# room_interface.net
KiCad netlist of a schematic drawn in EAGLE
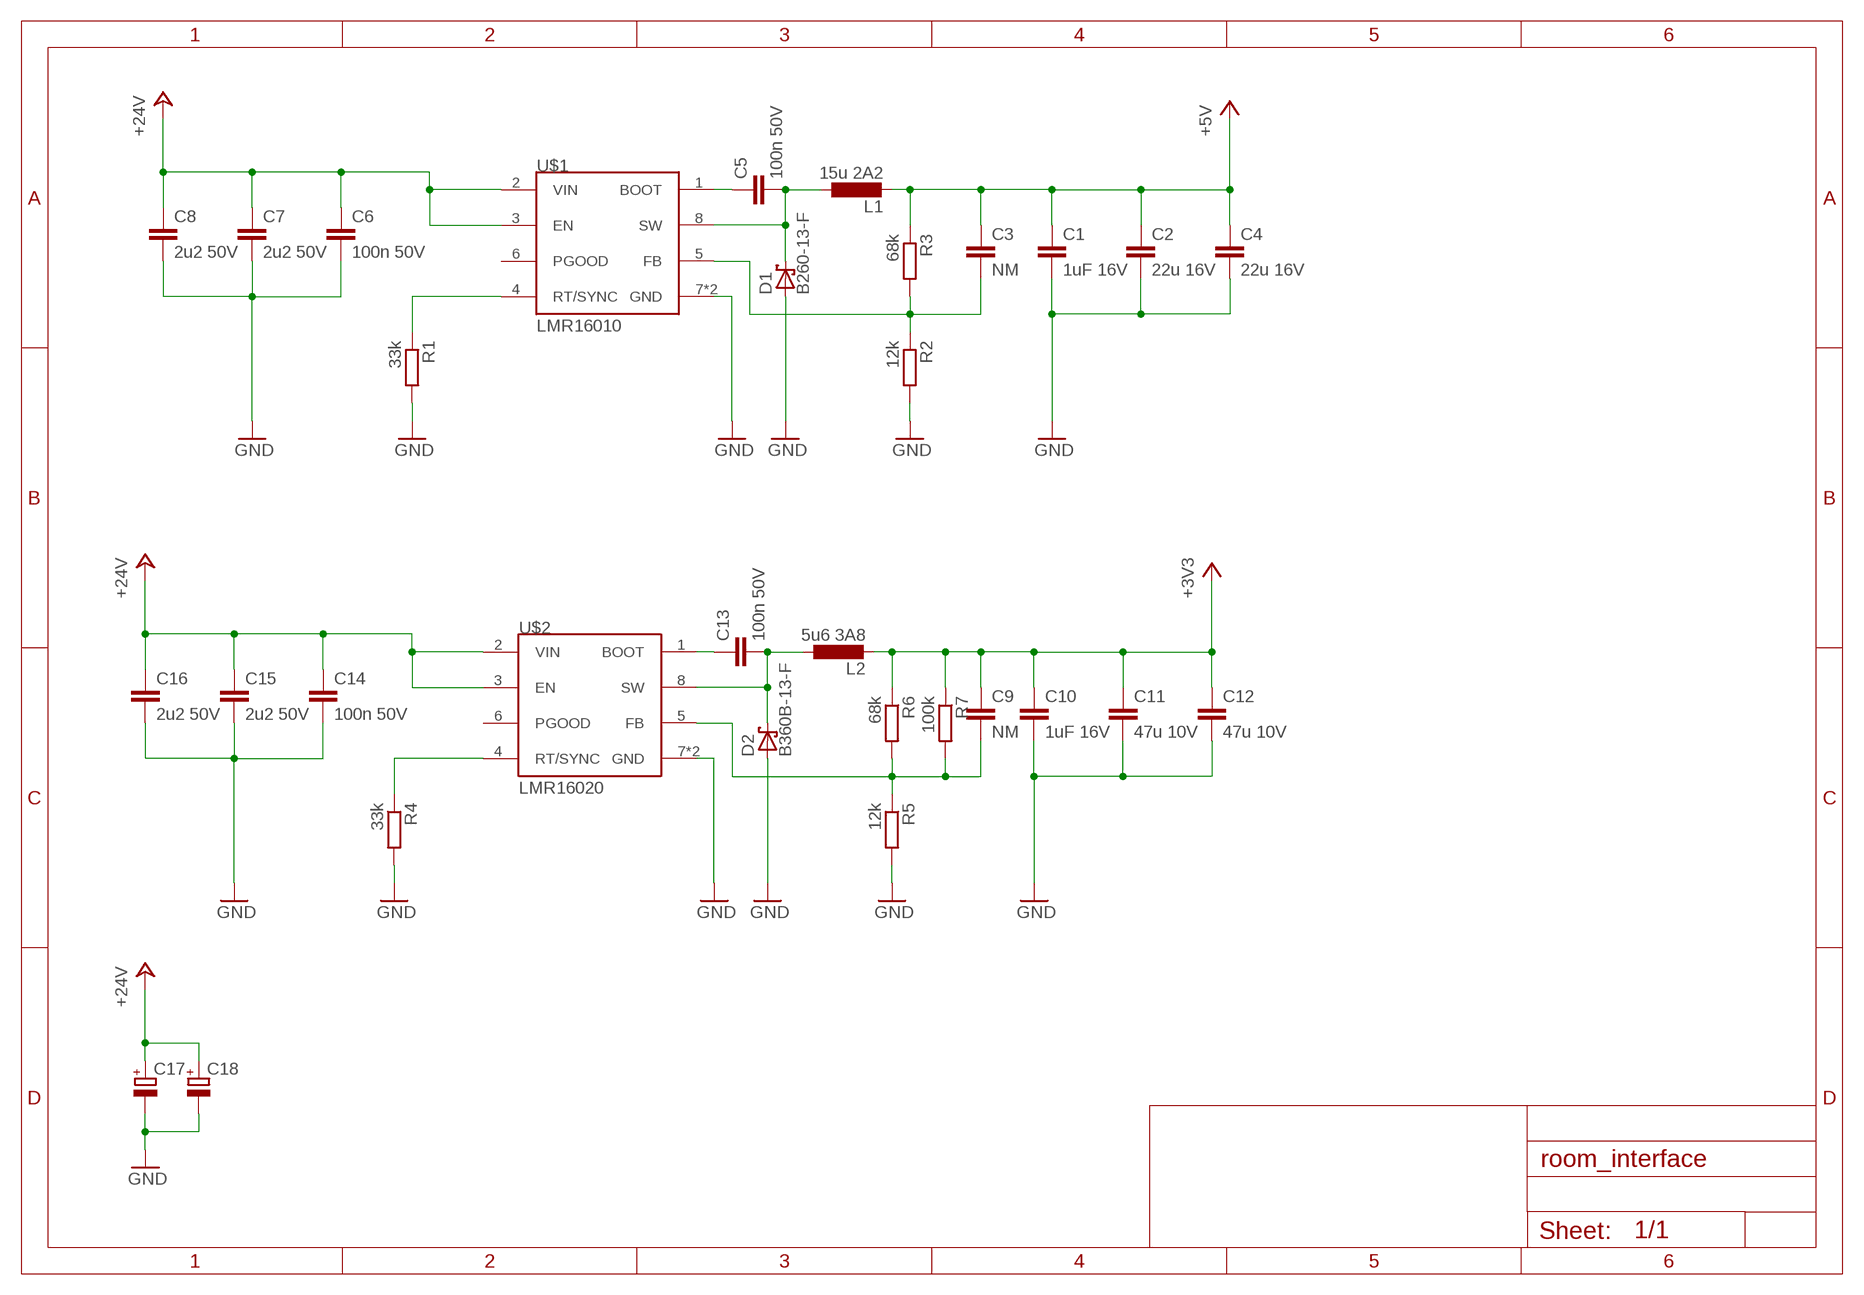
[diagram p0: schematic, sheet 1]

(export (version "E")
  (design (tool "Eeschema 10.0.6"))
  (components
    (comp (ref "C1")
      (value "1uF 16V")
      (footprint "eagle-import:C0805")
      (libsource (lib "eagle-import") (part "C-EUC0805"))
    )
    (comp (ref "C2")
      (value "22u 16V")
      (footprint "eagle-import:C1210")
      (libsource (lib "eagle-import") (part "C-EUC1210"))
    )
    (comp (ref "C3")
      (value "NM")
      (footprint "eagle-import:C1206")
      (libsource (lib "eagle-import") (part "C-EUC1206"))
    )
    (comp (ref "C4")
      (value "22u 16V")
      (footprint "eagle-import:C1210")
      (libsource (lib "eagle-import") (part "C-EUC1210"))
    )
    (comp (ref "C5")
      (value "100n 50V")
      (footprint "eagle-import:C1206")
      (libsource (lib "eagle-import") (part "C-EUC1206"))
    )
    (comp (ref "C6")
      (value "100n 50V")
      (footprint "eagle-import:C1206")
      (libsource (lib "eagle-import") (part "C-EUC1206"))
    )
    (comp (ref "C7")
      (value "2u2 50V")
      (footprint "eagle-import:C1206")
      (libsource (lib "eagle-import") (part "C-EUC1206"))
    )
    (comp (ref "C8")
      (value "2u2 50V")
      (footprint "eagle-import:C1206")
      (libsource (lib "eagle-import") (part "C-EUC1206"))
    )
    (comp (ref "C9")
      (value "NM")
      (footprint "eagle-import:C1206")
      (libsource (lib "eagle-import") (part "C-EUC1206"))
    )
    (comp (ref "C10")
      (value "1uF 16V")
      (footprint "eagle-import:C0805")
      (libsource (lib "eagle-import") (part "C-EUC0805"))
    )
    (comp (ref "C11")
      (value "47u 10V")
      (footprint "eagle-import:C1210")
      (libsource (lib "eagle-import") (part "C-EUC1210"))
    )
    (comp (ref "C12")
      (value "47u 10V")
      (footprint "eagle-import:C1210")
      (libsource (lib "eagle-import") (part "C-EUC1210"))
    )
    (comp (ref "C13")
      (value "100n 50V")
      (footprint "eagle-import:C1206")
      (libsource (lib "eagle-import") (part "C-EUC1206"))
    )
    (comp (ref "C14")
      (value "100n 50V")
      (footprint "eagle-import:C1206")
      (libsource (lib "eagle-import") (part "C-EUC1206"))
    )
    (comp (ref "C15")
      (value "2u2 50V")
      (footprint "eagle-import:C1206")
      (libsource (lib "eagle-import") (part "C-EUC1206"))
    )
    (comp (ref "C16")
      (value "2u2 50V")
      (footprint "eagle-import:C1206")
      (libsource (lib "eagle-import") (part "C-EUC1206"))
    )
    (comp (ref "C17")
      (value "CPOL-EUUD-5X5,8")
      (footprint "eagle-import:UD-5X5,8_NICHICON")
      (libsource (lib "eagle-import") (part "CPOL-EUUD-5X5,8"))
    )
    (comp (ref "C18")
      (value "CPOL-EUUD-5X5,8")
      (footprint "eagle-import:UD-5X5,8_NICHICON")
      (libsource (lib "eagle-import") (part "CPOL-EUUD-5X5,8"))
    )
    (comp (ref "D1")
      (value "B260-13-F")
      (footprint "eagle-import:SMB")
      (libsource (lib "eagle-import") (part "MBRS130LT3"))
    )
    (comp (ref "D2")
      (value "B360B-13-F")
      (footprint "eagle-import:SMB")
      (libsource (lib "eagle-import") (part "MBRS130LT3"))
    )
    (comp (ref "L1")
      (value "15u 2A2")
      (footprint "eagle-import:SLF10145T-150M2R2-PF")
      (libsource (lib "eagle-import") (part "SLF10145T-150M2R2-PF"))
    )
    (comp (ref "L2")
      (value "5u6 3A8")
      (footprint "eagle-import:SLF10145T-150M2R2-PF")
      (libsource (lib "eagle-import") (part "SLF10145T-150M2R2-PF"))
    )
    (comp (ref "R1")
      (value "33k")
      (footprint "eagle-import:R1206")
      (libsource (lib "eagle-import") (part "R-EU_R1206"))
    )
    (comp (ref "R2")
      (value "12k")
      (footprint "eagle-import:R1206")
      (libsource (lib "eagle-import") (part "R-EU_R1206"))
    )
    (comp (ref "R3")
      (value "68k")
      (footprint "eagle-import:R1206")
      (libsource (lib "eagle-import") (part "R-EU_R1206"))
    )
    (comp (ref "R4")
      (value "33k")
      (footprint "eagle-import:R1206")
      (libsource (lib "eagle-import") (part "R-EU_R1206"))
    )
    (comp (ref "R5")
      (value "12k")
      (footprint "eagle-import:R1206")
      (libsource (lib "eagle-import") (part "R-EU_R1206"))
    )
    (comp (ref "R6")
      (value "68k")
      (footprint "eagle-import:R1206")
      (libsource (lib "eagle-import") (part "R-EU_R1206"))
    )
    (comp (ref "R7")
      (value "100k")
      (footprint "eagle-import:R1206")
      (libsource (lib "eagle-import") (part "R-EU_R1206"))
    )
    (comp (ref "U$1")
      (value "LMR16010")
      (footprint "eagle-import:SOIC127P600X170-8N")
      (libsource (lib "eagle-import") (part "LMR16010"))
    )
    (comp (ref "U$2")
      (value "LMR16020")
      (footprint "eagle-import:SOIC127P600X170-8N")
      (libsource (lib "eagle-import") (part "LMR16020"))
    )
  )
  (nets
    (net (code "1") (name "+3V3") (class "Default")
      (node (ref "C10") (pin "1") (pinfunction "1_1") (pintype "passive"))
      (node (ref "C11") (pin "1") (pinfunction "1_1") (pintype "passive"))
      (node (ref "C12") (pin "1") (pinfunction "1_1") (pintype "passive"))
      (node (ref "C9") (pin "1") (pinfunction "1_1") (pintype "passive"))
      (node (ref "L2") (pin "P$2") (pinfunction "2_P$2") (pintype "passive"))
      (node (ref "R6") (pin "1") (pinfunction "1_1") (pintype "passive"))
      (node (ref "R7") (pin "1") (pinfunction "1_1") (pintype "passive"))
    )
    (net (code "2") (name "+5V") (class "Default")
      (node (ref "C1") (pin "1") (pinfunction "1_1") (pintype "passive"))
      (node (ref "C2") (pin "1") (pinfunction "1_1") (pintype "passive"))
      (node (ref "C3") (pin "1") (pinfunction "1_1") (pintype "passive"))
      (node (ref "C4") (pin "1") (pinfunction "1_1") (pintype "passive"))
      (node (ref "L1") (pin "P$2") (pinfunction "2_P$2") (pintype "passive"))
      (node (ref "R3") (pin "1") (pinfunction "1_1") (pintype "passive"))
    )
    (net (code "3") (name "+24V") (class "Default")
      (node (ref "C14") (pin "1") (pinfunction "1_1") (pintype "passive"))
      (node (ref "C15") (pin "1") (pinfunction "1_1") (pintype "passive"))
      (node (ref "C16") (pin "1") (pinfunction "1_1") (pintype "passive"))
      (node (ref "C17") (pin "+") (pinfunction "+_+") (pintype "passive"))
      (node (ref "C18") (pin "+") (pinfunction "+_+") (pintype "passive"))
      (node (ref "C6") (pin "1") (pinfunction "1_1") (pintype "passive"))
      (node (ref "C7") (pin "1") (pinfunction "1_1") (pintype "passive"))
      (node (ref "C8") (pin "1") (pinfunction "1_1") (pintype "passive"))
      (node (ref "U$1") (pin "2") (pinfunction "VIN_2") (pintype "power_in"))
      (node (ref "U$1") (pin "3") (pinfunction "EN_3") (pintype "input"))
      (node (ref "U$2") (pin "2") (pinfunction "VIN_2") (pintype "power_in"))
      (node (ref "U$2") (pin "3") (pinfunction "EN_3") (pintype "input"))
    )
    (net (code "4") (name "GND") (class "Default")
      (node (ref "C1") (pin "2") (pinfunction "2_2") (pintype "passive"))
      (node (ref "C10") (pin "2") (pinfunction "2_2") (pintype "passive"))
      (node (ref "C11") (pin "2") (pinfunction "2_2") (pintype "passive"))
      (node (ref "C12") (pin "2") (pinfunction "2_2") (pintype "passive"))
      (node (ref "C14") (pin "2") (pinfunction "2_2") (pintype "passive"))
      (node (ref "C15") (pin "2") (pinfunction "2_2") (pintype "passive"))
      (node (ref "C16") (pin "2") (pinfunction "2_2") (pintype "passive"))
      (node (ref "C17") (pin "-") (pinfunction "-_-") (pintype "passive"))
      (node (ref "C18") (pin "-") (pinfunction "-_-") (pintype "passive"))
      (node (ref "C2") (pin "2") (pinfunction "2_2") (pintype "passive"))
      (node (ref "C4") (pin "2") (pinfunction "2_2") (pintype "passive"))
      (node (ref "C6") (pin "2") (pinfunction "2_2") (pintype "passive"))
      (node (ref "C7") (pin "2") (pinfunction "2_2") (pintype "passive"))
      (node (ref "C8") (pin "2") (pinfunction "2_2") (pintype "passive"))
      (node (ref "D1") (pin "A") (pinfunction "A_A") (pintype "passive"))
      (node (ref "D2") (pin "A") (pinfunction "A_A") (pintype "passive"))
      (node (ref "R1") (pin "2") (pinfunction "2_2") (pintype "passive"))
      (node (ref "R2") (pin "2") (pinfunction "2_2") (pintype "passive"))
      (node (ref "R4") (pin "2") (pinfunction "2_2") (pintype "passive"))
      (node (ref "R5") (pin "2") (pinfunction "2_2") (pintype "passive"))
      (node (ref "U$1") (pin "7") (pinfunction "GND_7") (pintype "power_in"))
      (node (ref "U$1") (pin "9") (pinfunction "GND_9") (pintype "power_in"))
      (node (ref "U$2") (pin "7") (pinfunction "GND_7") (pintype "power_in"))
      (node (ref "U$2") (pin "9") (pinfunction "GND_9") (pintype "power_in"))
    )
    (net (code "5") (name "Net-(L1-1)") (class "Default")
      (node (ref "C5") (pin "2") (pinfunction "2_2") (pintype "passive"))
      (node (ref "D1") (pin "C") (pinfunction "C_C") (pintype "passive"))
      (node (ref "L1") (pin "P$1") (pinfunction "1_P$1") (pintype "passive"))
      (node (ref "U$1") (pin "8") (pinfunction "SW_8") (pintype "output"))
    )
    (net (code "6") (name "Net-(L2-1)") (class "Default")
      (node (ref "C13") (pin "2") (pinfunction "2_2") (pintype "passive"))
      (node (ref "D2") (pin "C") (pinfunction "C_C") (pintype "passive"))
      (node (ref "L2") (pin "P$1") (pinfunction "1_P$1") (pintype "passive"))
      (node (ref "U$2") (pin "8") (pinfunction "SW_8") (pintype "output"))
    )
    (net (code "7") (name "Net-(U$1-BOOT)") (class "Default")
      (node (ref "C5") (pin "1") (pinfunction "1_1") (pintype "passive"))
      (node (ref "U$1") (pin "1") (pinfunction "BOOT_1") (pintype "power_in"))
    )
    (net (code "8") (name "Net-(U$1-FB)") (class "Default")
      (node (ref "C3") (pin "2") (pinfunction "2_2") (pintype "passive"))
      (node (ref "R2") (pin "1") (pinfunction "1_1") (pintype "passive"))
      (node (ref "R3") (pin "2") (pinfunction "2_2") (pintype "passive"))
      (node (ref "U$1") (pin "5") (pinfunction "FB_5") (pintype "input"))
    )
    (net (code "9") (name "Net-(U$1-RT{slash}SYNC)") (class "Default")
      (node (ref "R1") (pin "1") (pinfunction "1_1") (pintype "passive"))
      (node (ref "U$1") (pin "4") (pinfunction "RT/SYNC_4") (pintype "input"))
    )
    (net (code "10") (name "Net-(U$2-BOOT)") (class "Default")
      (node (ref "C13") (pin "1") (pinfunction "1_1") (pintype "passive"))
      (node (ref "U$2") (pin "1") (pinfunction "BOOT_1") (pintype "power_in"))
    )
    (net (code "11") (name "Net-(U$2-FB)") (class "Default")
      (node (ref "C9") (pin "2") (pinfunction "2_2") (pintype "passive"))
      (node (ref "R5") (pin "1") (pinfunction "1_1") (pintype "passive"))
      (node (ref "R6") (pin "2") (pinfunction "2_2") (pintype "passive"))
      (node (ref "R7") (pin "2") (pinfunction "2_2") (pintype "passive"))
      (node (ref "U$2") (pin "5") (pinfunction "FB_5") (pintype "input"))
    )
    (net (code "12") (name "Net-(U$2-RT{slash}SYNC)") (class "Default")
      (node (ref "R4") (pin "1") (pinfunction "1_1") (pintype "passive"))
      (node (ref "U$2") (pin "4") (pinfunction "RT/SYNC_4") (pintype "input"))
    )
    (net (code "13") (name "unconnected-(U$1-PGOOD-Pad6)") (class "Default")
      (node (ref "U$1") (pin "6") (pinfunction "PGOOD_6") (pintype "output"))
    )
    (net (code "14") (name "unconnected-(U$2-PGOOD-Pad6)") (class "Default")
      (node (ref "U$2") (pin "6") (pinfunction "PGOOD_6") (pintype "output"))
    )
  )
)
